# warm_floor.net
KiCad netlist of a schematic drawn in EAGLE
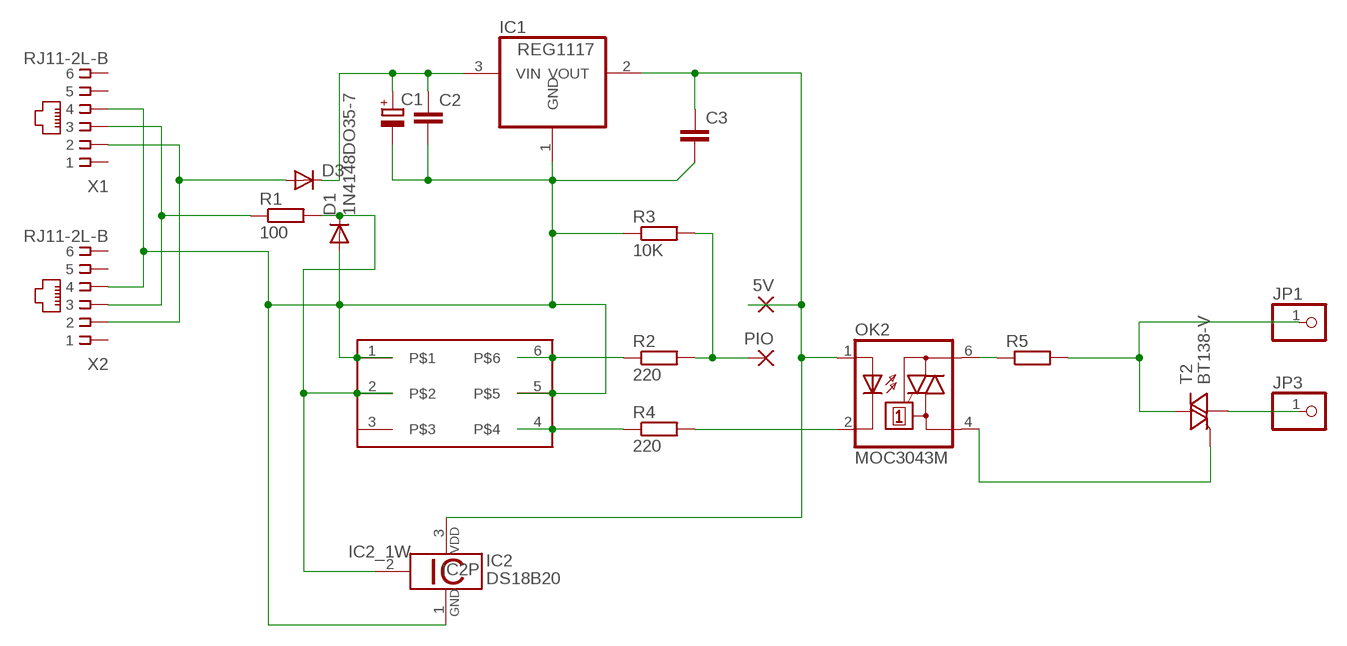
[diagram p0: schematic, sheet 1]

(export (version "E")
  (design (tool "Eeschema 10.0.6"))
  (components
    (comp (ref "5V")
      (value "1,6/0,8")
      (footprint "eagle-import:1,6_0,8")
      (libsource (lib "eagle-import") (part "1,6/0,8"))
    )
    (comp (ref "C1")
      (value "CPOL-EUE5-10.5")
      (footprint "eagle-import:E5-10,5")
      (libsource (lib "eagle-import") (part "CPOL-EUE5-10.5"))
    )
    (comp (ref "C2")
      (value "C-EUC1206")
      (footprint "eagle-import:C1206")
      (libsource (lib "eagle-import") (part "C-EUC1206"))
    )
    (comp (ref "C3")
      (value "C-EUC1206")
      (footprint "eagle-import:C1206")
      (libsource (lib "eagle-import") (part "C-EUC1206"))
    )
    (comp (ref "D1")
      (value "1N4148DO35-7")
      (footprint "eagle-import:DO35-7")
      (libsource (lib "eagle-import") (part "1N4148DO35-7"))
    )
    (comp (ref "D3")
      (value "DIODE-MINIMELF")
      (footprint "eagle-import:MINIMELF")
      (libsource (lib "eagle-import") (part "DIODE-MINIMELF"))
    )
    (comp (ref "DS2413")
      (value "DS2413P")
      (footprint "eagle-import:TSOC6")
      (libsource (lib "eagle-import") (part "DS2413P"))
    )
    (comp (ref "IC1")
      (value "REG1117")
      (footprint "eagle-import:SOT223")
      (libsource (lib "eagle-import") (part "REG1117"))
    )
    (comp (ref "IC2")
      (value "DS18B20")
      (footprint "eagle-import:TO92-")
      (libsource (lib "eagle-import") (part "DS18B20"))
    )
    (comp (ref "JP1")
      (value "PINHD-1X1")
      (footprint "eagle-import:1X01")
      (libsource (lib "eagle-import") (part "PINHD-1X1"))
    )
    (comp (ref "JP3")
      (value "PINHD-1X1")
      (footprint "eagle-import:1X01")
      (libsource (lib "eagle-import") (part "PINHD-1X1"))
    )
    (comp (ref "OK2")
      (value "MOC3043M")
      (footprint "eagle-import:DIL06")
      (libsource (lib "eagle-import") (part "MOC3043M"))
    )
    (comp (ref "PIO")
      (value "1,6/0,8")
      (footprint "eagle-import:1,6_0,8")
      (libsource (lib "eagle-import") (part "1,6/0,8"))
    )
    (comp (ref "R1")
      (value "100")
      (footprint "eagle-import:M1206")
      (libsource (lib "eagle-import") (part "R-EU_M1206"))
    )
    (comp (ref "R2")
      (value "220")
      (footprint "eagle-import:M1206")
      (libsource (lib "eagle-import") (part "R-EU_M1206"))
    )
    (comp (ref "R3")
      (value "10K")
      (footprint "eagle-import:M1206")
      (libsource (lib "eagle-import") (part "R-EU_M1206"))
    )
    (comp (ref "R4")
      (value "220")
      (footprint "eagle-import:M1206")
      (libsource (lib "eagle-import") (part "R-EU_M1206"))
    )
    (comp (ref "R5")
      (value "R-EU_M1206")
      (footprint "eagle-import:M1206")
      (libsource (lib "eagle-import") (part "R-EU_M1206"))
    )
    (comp (ref "T2")
      (value "BT138-V")
      (footprint "eagle-import:TO220BV")
      (libsource (lib "eagle-import") (part "BT138-V"))
    )
    (comp (ref "X1")
      (value "RJ11-2L-B")
      (footprint "eagle-import:RJ11-NO_SHIELD")
      (fields (field (name "MF") "TYCO ELECTRONICS"))
      (libsource (lib "eagle-import") (part "RJ11-2L-B"))
    )
    (comp (ref "X2")
      (value "RJ11-2L-B")
      (footprint "eagle-import:RJ11-NO_SHIELD")
      (fields (field (name "MF") "TYCO ELECTRONICS"))
      (libsource (lib "eagle-import") (part "RJ11-2L-B"))
    )
  )
  (nets
    (net (code "1") (name "Net-(5V-P)") (class "Default")
      (node (ref "5V") (pin "1") (pinfunction "P_1") (pintype "passive"))
      (node (ref "C3") (pin "1") (pinfunction "1_1") (pintype "passive"))
      (node (ref "IC1") (pin "2") (pinfunction "VOUT_2") (pintype "output"))
      (node (ref "IC2") (pin "3") (pinfunction "VDD_3") (pintype "power_in"))
      (node (ref "OK2") (pin "1") (pinfunction "A_1") (pintype "passive"))
    )
    (net (code "2") (name "Net-(D3-PadA)") (class "Default")
      (node (ref "D3") (pin "A") (pinfunction "A_A") (pintype "passive"))
      (node (ref "X1") (pin "2") (pinfunction "2_2") (pintype "passive"))
      (node (ref "X2") (pin "2") (pinfunction "2_2") (pintype "passive"))
    )
    (net (code "3") (name "Net-(DS2413-P$1)") (class "Default")
      (node (ref "C1") (pin "-") (pinfunction "-_-") (pintype "passive"))
      (node (ref "C2") (pin "2") (pinfunction "2_2") (pintype "passive"))
      (node (ref "C3") (pin "2") (pinfunction "2_2") (pintype "passive"))
      (node (ref "D1") (pin "A") (pinfunction "A_A") (pintype "passive"))
      (node (ref "DS2413") (pin "1") (pinfunction "P$1_1") (pintype "bidirectional"))
      (node (ref "DS2413") (pin "5") (pinfunction "P$5_5") (pintype "bidirectional"))
      (node (ref "IC1") (pin "1") (pinfunction "GND_1") (pintype "power_in"))
      (node (ref "IC2") (pin "1") (pinfunction "GND_1") (pintype "power_in"))
      (node (ref "R3") (pin "1") (pinfunction "1_1") (pintype "passive"))
      (node (ref "X1") (pin "4") (pinfunction "4_4") (pintype "passive"))
      (node (ref "X2") (pin "4") (pinfunction "4_4") (pintype "passive"))
    )
    (net (code "4") (name "Net-(DS2413-P$2)") (class "Default")
      (node (ref "D1") (pin "C") (pinfunction "C_C") (pintype "passive"))
      (node (ref "DS2413") (pin "2") (pinfunction "P$2_2") (pintype "bidirectional"))
      (node (ref "IC2") (pin "2") (pinfunction "1W_2") (pintype "power_in"))
      (node (ref "R1") (pin "2") (pinfunction "2_2") (pintype "passive"))
    )
    (net (code "5") (name "Net-(DS2413-P$4)") (class "Default")
      (node (ref "DS2413") (pin "4") (pinfunction "P$4_4") (pintype "bidirectional"))
      (node (ref "R4") (pin "1") (pinfunction "1_1") (pintype "passive"))
    )
    (net (code "6") (name "Net-(DS2413-P$6)") (class "Default")
      (node (ref "DS2413") (pin "6") (pinfunction "P$6_6") (pintype "bidirectional"))
      (node (ref "R2") (pin "1") (pinfunction "1_1") (pintype "passive"))
    )
    (net (code "7") (name "Net-(IC1-VIN)") (class "Default")
      (node (ref "C1") (pin "+") (pinfunction "+_+") (pintype "passive"))
      (node (ref "C2") (pin "1") (pinfunction "1_1") (pintype "passive"))
      (node (ref "D3") (pin "C") (pinfunction "C_C") (pintype "passive"))
      (node (ref "IC1") (pin "3") (pinfunction "VIN_3") (pintype "input"))
    )
    (net (code "8") (name "Net-(OK2-A1)") (class "Default")
      (node (ref "OK2") (pin "4") (pinfunction "A1_4") (pintype "passive"))
      (node (ref "T2") (pin "G") (pinfunction "G_G") (pintype "passive"))
    )
    (net (code "9") (name "Net-(OK2-A2)") (class "Default")
      (node (ref "OK2") (pin "6") (pinfunction "A2_6") (pintype "passive"))
      (node (ref "R5") (pin "1") (pinfunction "1_1") (pintype "passive"))
    )
    (net (code "10") (name "Net-(OK2-C)") (class "Default")
      (node (ref "OK2") (pin "2") (pinfunction "C_2") (pintype "passive"))
      (node (ref "R4") (pin "2") (pinfunction "2_2") (pintype "passive"))
    )
    (net (code "11") (name "Net-(PIO-P)") (class "Default")
      (node (ref "PIO") (pin "1") (pinfunction "P_1") (pintype "passive"))
      (node (ref "R2") (pin "2") (pinfunction "2_2") (pintype "passive"))
      (node (ref "R3") (pin "2") (pinfunction "2_2") (pintype "passive"))
    )
    (net (code "12") (name "Net-(R1-Pad1)") (class "Default")
      (node (ref "R1") (pin "1") (pinfunction "1_1") (pintype "passive"))
      (node (ref "X1") (pin "3") (pinfunction "3_3") (pintype "passive"))
      (node (ref "X2") (pin "3") (pinfunction "3_3") (pintype "passive"))
    )
    (net (code "13") (name "Net-(T2-A1)") (class "Default")
      (node (ref "JP3") (pin "1") (pinfunction "1_1") (pintype "passive"))
      (node (ref "T2") (pin "T1") (pinfunction "A1_T1") (pintype "passive"))
    )
    (net (code "14") (name "Net-(T2-A2)") (class "Default")
      (node (ref "JP1") (pin "1") (pinfunction "1_1") (pintype "passive"))
      (node (ref "R5") (pin "2") (pinfunction "2_2") (pintype "passive"))
      (node (ref "T2") (pin "T2") (pinfunction "A2_T2") (pintype "passive"))
    )
    (net (code "15") (name "unconnected-(DS2413-P$3-Pad3)") (class "Default")
      (node (ref "DS2413") (pin "3") (pinfunction "P$3_3") (pintype "bidirectional"))
    )
    (net (code "16") (name "unconnected-(X1-Pad1)") (class "Default")
      (node (ref "X1") (pin "1") (pinfunction "1_1") (pintype "passive"))
    )
    (net (code "17") (name "unconnected-(X1-Pad5)") (class "Default")
      (node (ref "X1") (pin "5") (pinfunction "5_5") (pintype "passive"))
    )
    (net (code "18") (name "unconnected-(X1-Pad6)") (class "Default")
      (node (ref "X1") (pin "6") (pinfunction "6_6") (pintype "passive"))
    )
    (net (code "19") (name "unconnected-(X2-Pad1)") (class "Default")
      (node (ref "X2") (pin "1") (pinfunction "1_1") (pintype "passive"))
    )
    (net (code "20") (name "unconnected-(X2-Pad5)") (class "Default")
      (node (ref "X2") (pin "5") (pinfunction "5_5") (pintype "passive"))
    )
    (net (code "21") (name "unconnected-(X2-Pad6)") (class "Default")
      (node (ref "X2") (pin "6") (pinfunction "6_6") (pintype "passive"))
    )
  )
)
